# encoder.net
KiCad netlist of a schematic drawn in EAGLE
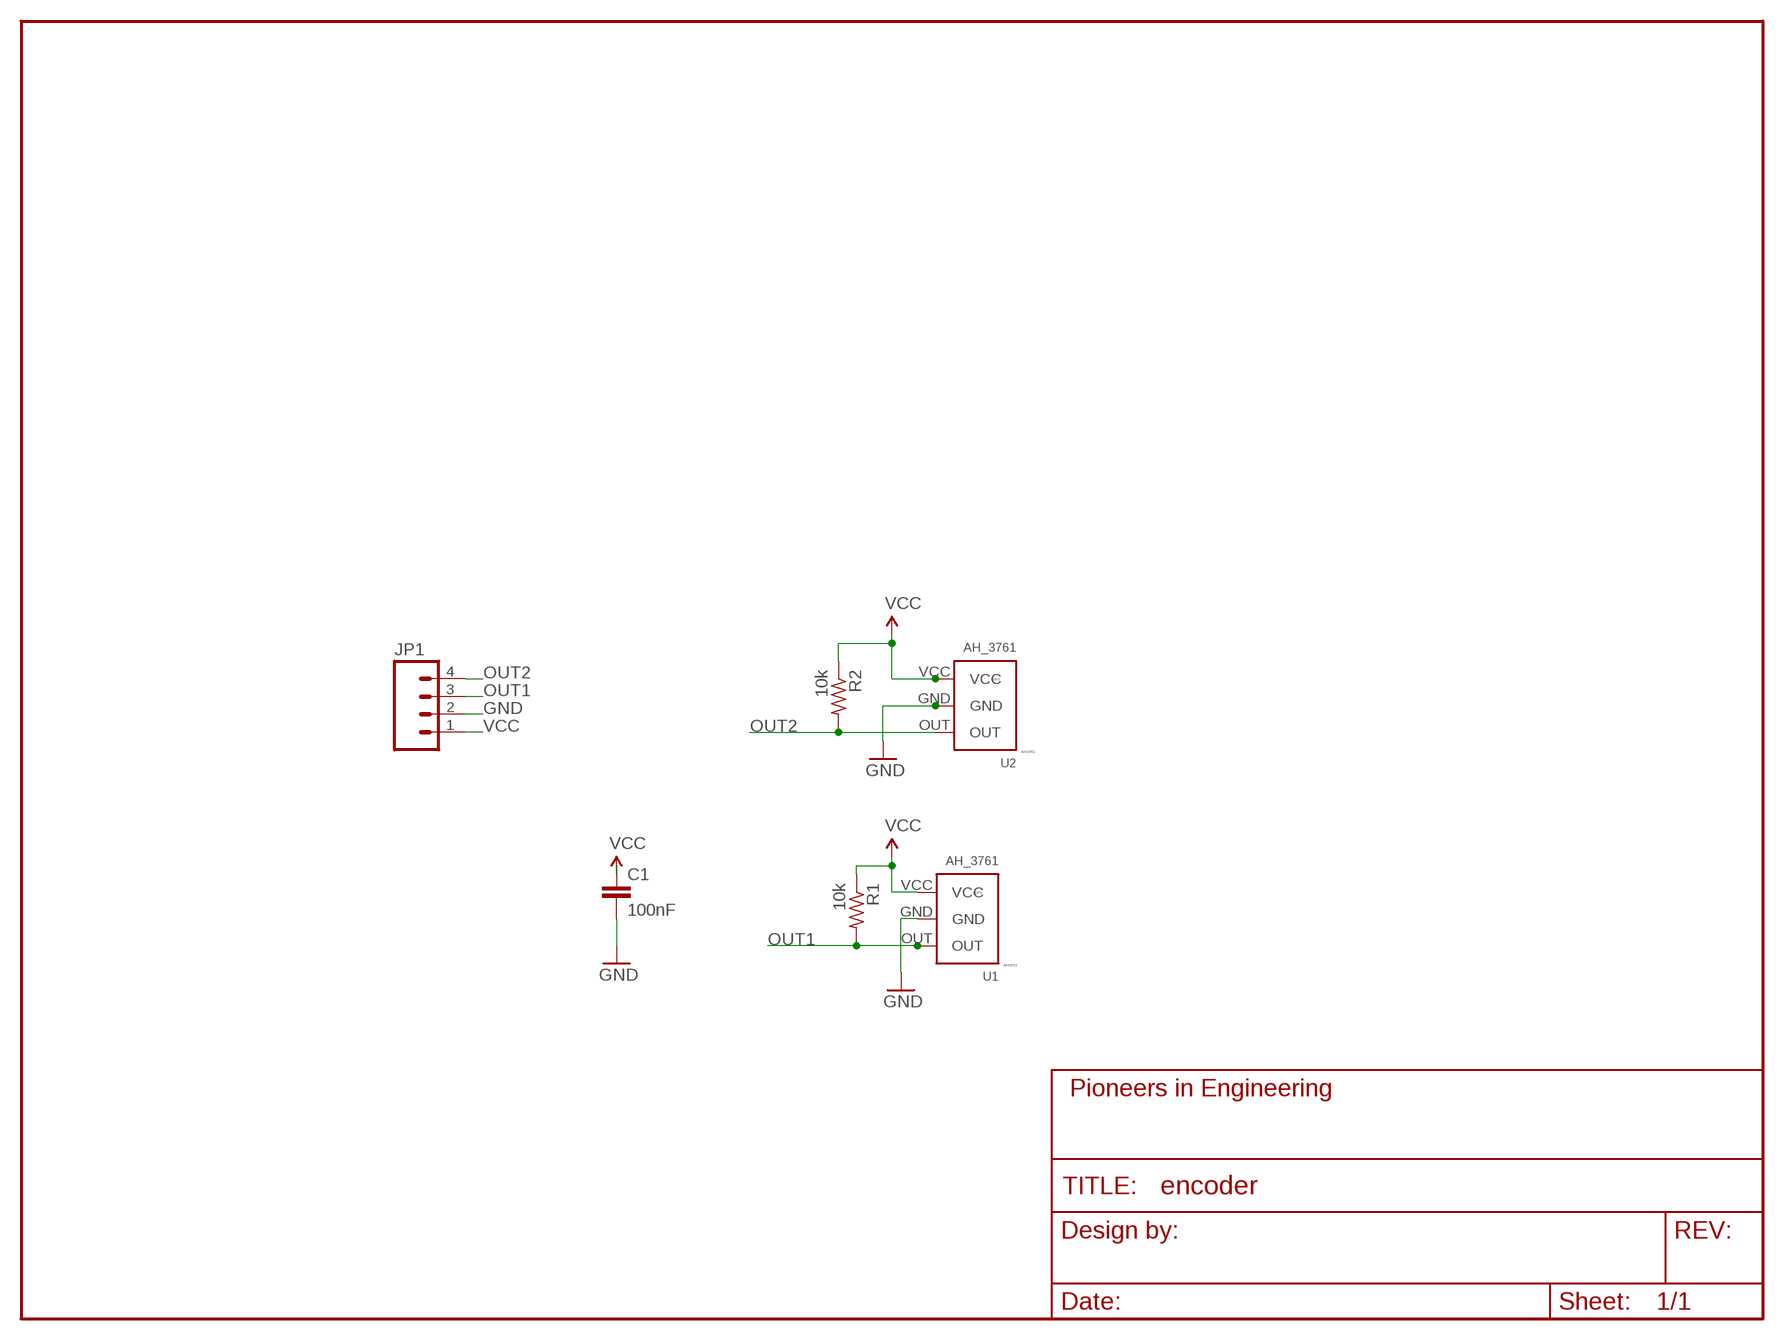
[diagram p0: schematic, sheet 1]

(export (version "E")
  (design (tool "Eeschema 10.0.6"))
  (components
    (comp (ref "C1")
      (value "100nF")
      (footprint "eagle-import:0603-CAP")
      (libsource (lib "eagle-import") (part "CAP0603-CAP"))
    )
    (comp (ref "JP1")
      (value "M04POLAR")
      (footprint "eagle-import:MOLEX-1X4")
      (libsource (lib "eagle-import") (part "M04POLAR"))
    )
    (comp (ref "R1")
      (value "10k")
      (footprint "eagle-import:R0603")
      (libsource (lib "eagle-import") (part "R-US_R0603"))
    )
    (comp (ref "R2")
      (value "10k")
      (footprint "eagle-import:R0603")
      (libsource (lib "eagle-import") (part "R-US_R0603"))
    )
    (comp (ref "U1")
      (value "AH_3761")
      (footprint "eagle-import:SIP3")
      (libsource (lib "eagle-import") (part "AH_3761"))
    )
    (comp (ref "U2")
      (value "AH_3761")
      (footprint "eagle-import:SIP3")
      (libsource (lib "eagle-import") (part "AH_3761"))
    )
  )
  (nets
    (net (code "1") (name "/OUT1") (class "Default")
      (node (ref "JP1") (pin "3") (pinfunction "3_3") (pintype "passive"))
      (node (ref "R1") (pin "2") (pinfunction "2_2") (pintype "passive"))
      (node (ref "U1") (pin "OUT") (pinfunction "OUT_OUT") (pintype "bidirectional"))
    )
    (net (code "2") (name "/OUT2") (class "Default")
      (node (ref "JP1") (pin "4") (pinfunction "4_4") (pintype "passive"))
      (node (ref "R2") (pin "2") (pinfunction "2_2") (pintype "passive"))
      (node (ref "U2") (pin "OUT") (pinfunction "OUT_OUT") (pintype "bidirectional"))
    )
    (net (code "3") (name "GND") (class "Default")
      (node (ref "C1") (pin "2") (pinfunction "2_2") (pintype "passive"))
      (node (ref "JP1") (pin "2") (pinfunction "2_2") (pintype "passive"))
      (node (ref "U1") (pin "GND") (pinfunction "GND_GND") (pintype "power_in"))
      (node (ref "U2") (pin "GND") (pinfunction "GND_GND") (pintype "power_in"))
    )
    (net (code "4") (name "VCC") (class "Default")
      (node (ref "C1") (pin "1") (pinfunction "1_1") (pintype "passive"))
      (node (ref "JP1") (pin "1") (pinfunction "1_1") (pintype "passive"))
      (node (ref "R1") (pin "1") (pinfunction "1_1") (pintype "passive"))
      (node (ref "R2") (pin "1") (pinfunction "1_1") (pintype "passive"))
      (node (ref "U1") (pin "VCC") (pinfunction "VCC_VCC") (pintype "power_in"))
      (node (ref "U2") (pin "VCC") (pinfunction "VCC_VCC") (pintype "power_in"))
    )
  )
)
